# unicorder-temp-mk-1_0.net
KiCad netlist of a schematic drawn in EAGLE
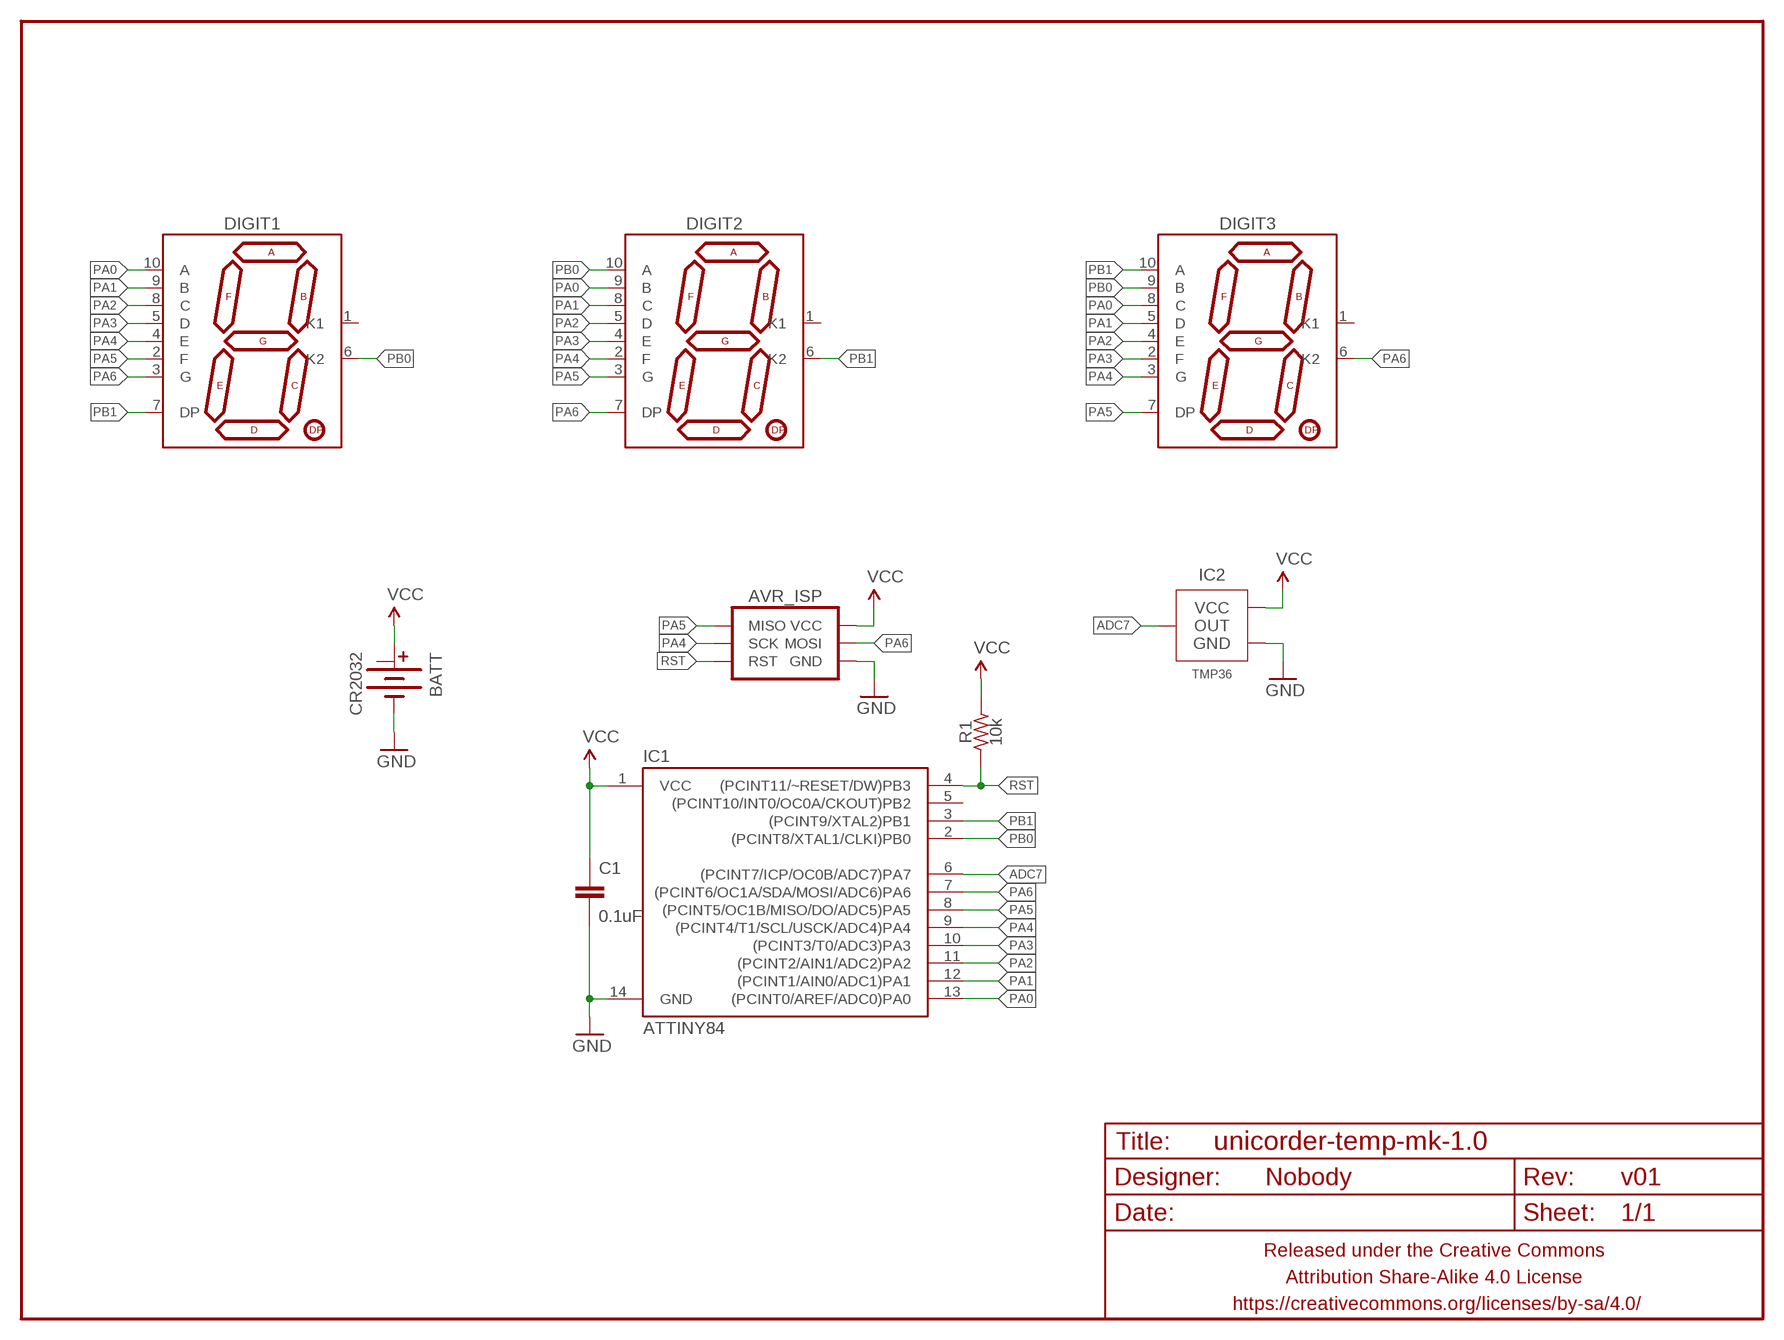
[diagram p0: schematic, sheet 1]

(export (version "E")
  (design (tool "Eeschema 10.0.6"))
  (components
    (comp (ref "AVR_ISP")
      (value "AVR_SPI_PRG_6PTH")
      (footprint "eagle-import:2X3")
      (libsource (lib "eagle-import") (part "AVR_SPI_PRG_6PTH"))
    )
    (comp (ref "BATT")
      (value "CR2032")
      (footprint "eagle-import:BATTCON_20MM_MINE")
      (libsource (lib "eagle-import") (part "BATTERY-COINCR2032_SMD"))
    )
    (comp (ref "C1")
      (value "0.1uF")
      (footprint "eagle-import:C025-024X044")
      (libsource (lib "eagle-import") (part "CAPACITOR-CERAMIC025-024X044"))
    )
    (comp (ref "DIGIT1")
      (value "7SEG_1DIGPTH-10MM")
      (footprint "eagle-import:7SEG_1DIG_10MM")
      (libsource (lib "eagle-import") (part "7SEG_1DIGPTH-10MM"))
    )
    (comp (ref "DIGIT2")
      (value "7SEG_1DIGPTH-10MM")
      (footprint "eagle-import:7SEG_1DIG_10MM")
      (libsource (lib "eagle-import") (part "7SEG_1DIGPTH-10MM"))
    )
    (comp (ref "DIGIT3")
      (value "7SEG_1DIGPTH-10MM")
      (footprint "eagle-import:7SEG_1DIG_10MM")
      (libsource (lib "eagle-import") (part "7SEG_1DIGPTH-10MM"))
    )
    (comp (ref "FRAME1")
      (value "FRAME-LETTERNO_PACKAGE")
      (footprint "eagle-import:DUMMY")
      (fields (field (name "DESIGNER") "Nobody"))
      (libsource (lib "eagle-import") (part "FRAME-LETTERNO_PACKAGE"))
    )
    (comp (ref "IC1")
      (value "ATTINY84")
      (footprint "eagle-import:DIL14")
      (libsource (lib "eagle-import") (part "ATTINY84ATTINY84-20PU"))
    )
    (comp (ref "IC2")
      (value "TMP36")
      (footprint "eagle-import:TO-92-AMMO")
      (libsource (lib "eagle-import") (part "TMP36TO-92"))
    )
    (comp (ref "R1")
      (value "10k")
      (footprint "eagle-import:RESISTOR-AXIAL-PTH-7.62MM")
      (libsource (lib "eagle-import") (part "RESISTORPTH-AXIAL-7.62MM"))
    )
  )
  (nets
    (net (code "1") (name "ADC7") (class "Default")
      (node (ref "IC1") (pin "6") (pinfunction "(PCINT7/ICP/OC0B/ADC7)PA7_6") (pintype "bidirectional"))
      (node (ref "IC2") (pin "2") (pinfunction "OUT_2") (pintype "bidirectional"))
    )
    (net (code "2") (name "GND") (class "Default")
      (node (ref "AVR_ISP") (pin "6") (pinfunction "GND_6") (pintype "passive"))
      (node (ref "BATT") (pin "BOTTOM") (pinfunction "-_BOTTOM") (pintype "bidirectional"))
      (node (ref "C1") (pin "2") (pinfunction "2_2") (pintype "passive"))
      (node (ref "IC1") (pin "14") (pinfunction "GND_14") (pintype "bidirectional"))
      (node (ref "IC2") (pin "3") (pinfunction "GND_3") (pintype "bidirectional"))
    )
    (net (code "3") (name "PA0") (class "Default")
      (node (ref "DIGIT1") (pin "10") (pinfunction "A_10") (pintype "bidirectional"))
      (node (ref "DIGIT2") (pin "9") (pinfunction "B_9") (pintype "bidirectional"))
      (node (ref "DIGIT3") (pin "8") (pinfunction "C_8") (pintype "bidirectional"))
      (node (ref "IC1") (pin "13") (pinfunction "(PCINT0/AREF/ADC0)PA0_13") (pintype "bidirectional"))
    )
    (net (code "4") (name "PA1") (class "Default")
      (node (ref "DIGIT1") (pin "9") (pinfunction "B_9") (pintype "bidirectional"))
      (node (ref "DIGIT2") (pin "8") (pinfunction "C_8") (pintype "bidirectional"))
      (node (ref "DIGIT3") (pin "5") (pinfunction "D_5") (pintype "bidirectional"))
      (node (ref "IC1") (pin "12") (pinfunction "(PCINT1/AIN0/ADC1)PA1_12") (pintype "bidirectional"))
    )
    (net (code "5") (name "PA2") (class "Default")
      (node (ref "DIGIT1") (pin "8") (pinfunction "C_8") (pintype "bidirectional"))
      (node (ref "DIGIT2") (pin "5") (pinfunction "D_5") (pintype "bidirectional"))
      (node (ref "DIGIT3") (pin "4") (pinfunction "E_4") (pintype "bidirectional"))
      (node (ref "IC1") (pin "11") (pinfunction "(PCINT2/AIN1/ADC2)PA2_11") (pintype "bidirectional"))
    )
    (net (code "6") (name "PA3") (class "Default")
      (node (ref "DIGIT1") (pin "5") (pinfunction "D_5") (pintype "bidirectional"))
      (node (ref "DIGIT2") (pin "4") (pinfunction "E_4") (pintype "bidirectional"))
      (node (ref "DIGIT3") (pin "2") (pinfunction "F_2") (pintype "bidirectional"))
      (node (ref "IC1") (pin "10") (pinfunction "(PCINT3/T0/ADC3)PA3_10") (pintype "bidirectional"))
    )
    (net (code "7") (name "PA4") (class "Default")
      (node (ref "AVR_ISP") (pin "3") (pinfunction "SCK_3") (pintype "passive"))
      (node (ref "DIGIT1") (pin "4") (pinfunction "E_4") (pintype "bidirectional"))
      (node (ref "DIGIT2") (pin "2") (pinfunction "F_2") (pintype "bidirectional"))
      (node (ref "DIGIT3") (pin "3") (pinfunction "G_3") (pintype "bidirectional"))
      (node (ref "IC1") (pin "9") (pinfunction "(PCINT4/T1/SCL/USCK/ADC4)PA4_9") (pintype "bidirectional"))
    )
    (net (code "8") (name "PA5") (class "Default")
      (node (ref "AVR_ISP") (pin "1") (pinfunction "MISO_1") (pintype "passive"))
      (node (ref "DIGIT1") (pin "2") (pinfunction "F_2") (pintype "bidirectional"))
      (node (ref "DIGIT2") (pin "3") (pinfunction "G_3") (pintype "bidirectional"))
      (node (ref "DIGIT3") (pin "7") (pinfunction "DP_7") (pintype "bidirectional"))
      (node (ref "IC1") (pin "8") (pinfunction "(PCINT5/OC1B/MISO/DO/ADC5)PA5_8") (pintype "bidirectional"))
    )
    (net (code "9") (name "PA6") (class "Default")
      (node (ref "AVR_ISP") (pin "4") (pinfunction "MOSI_4") (pintype "passive"))
      (node (ref "DIGIT1") (pin "3") (pinfunction "G_3") (pintype "bidirectional"))
      (node (ref "DIGIT2") (pin "7") (pinfunction "DP_7") (pintype "bidirectional"))
      (node (ref "DIGIT3") (pin "6") (pinfunction "K2_6") (pintype "bidirectional"))
      (node (ref "IC1") (pin "7") (pinfunction "(PCINT6/OC1A/SDA/MOSI/ADC6)PA6_7") (pintype "bidirectional"))
    )
    (net (code "10") (name "PB0") (class "Default")
      (node (ref "DIGIT1") (pin "6") (pinfunction "K2_6") (pintype "bidirectional"))
      (node (ref "DIGIT2") (pin "10") (pinfunction "A_10") (pintype "bidirectional"))
      (node (ref "DIGIT3") (pin "9") (pinfunction "B_9") (pintype "bidirectional"))
      (node (ref "IC1") (pin "2") (pinfunction "(PCINT8/XTAL1/CLKI)PB0_2") (pintype "bidirectional"))
    )
    (net (code "11") (name "PB1") (class "Default")
      (node (ref "DIGIT1") (pin "7") (pinfunction "DP_7") (pintype "bidirectional"))
      (node (ref "DIGIT2") (pin "6") (pinfunction "K2_6") (pintype "bidirectional"))
      (node (ref "DIGIT3") (pin "10") (pinfunction "A_10") (pintype "bidirectional"))
      (node (ref "IC1") (pin "3") (pinfunction "(PCINT9/XTAL2)PB1_3") (pintype "bidirectional"))
    )
    (net (code "12") (name "RST") (class "Default")
      (node (ref "AVR_ISP") (pin "5") (pinfunction "RST_5") (pintype "passive"))
      (node (ref "IC1") (pin "4") (pinfunction "(PCINT11/~{RESET/DW})PB3_4") (pintype "bidirectional"))
      (node (ref "R1") (pin "P$1") (pinfunction "1_P$1") (pintype "passive"))
    )
    (net (code "13") (name "VCC") (class "Default")
      (node (ref "AVR_ISP") (pin "2") (pinfunction "VCC_2") (pintype "passive"))
      (node (ref "BATT") (pin "TOP@1") (pinfunction "+_TOP@1") (pintype "bidirectional"))
      (node (ref "C1") (pin "1") (pinfunction "1_1") (pintype "passive"))
      (node (ref "IC1") (pin "1") (pinfunction "VCC_1") (pintype "bidirectional"))
      (node (ref "IC2") (pin "1") (pinfunction "VCC_1") (pintype "bidirectional"))
      (node (ref "R1") (pin "P$2") (pinfunction "2_P$2") (pintype "passive"))
    )
    (net (code "14") (name "unconnected-(BATT-+1-PadTOP@2)") (class "Default")
      (node (ref "BATT") (pin "TOP@2") (pinfunction "+1_TOP@2") (pintype "bidirectional"))
    )
    (net (code "15") (name "unconnected-(DIGIT1-K1-Pad1)") (class "Default")
      (node (ref "DIGIT1") (pin "1") (pinfunction "K1_1") (pintype "bidirectional"))
    )
    (net (code "16") (name "unconnected-(DIGIT2-K1-Pad1)") (class "Default")
      (node (ref "DIGIT2") (pin "1") (pinfunction "K1_1") (pintype "bidirectional"))
    )
    (net (code "17") (name "unconnected-(DIGIT3-K1-Pad1)") (class "Default")
      (node (ref "DIGIT3") (pin "1") (pinfunction "K1_1") (pintype "bidirectional"))
    )
    (net (code "18") (name "unconnected-(IC1-(PCINT10{slash}INT0{slash}OC0A{slash}CKOUT)PB2-Pad5)") (class "Default")
      (node (ref "IC1") (pin "5") (pinfunction "(PCINT10/INT0/OC0A/CKOUT)PB2_5") (pintype "bidirectional"))
    )
  )
)
